# Sheet2.net
KiCad netlist of a schematic drawn in Altium Designer
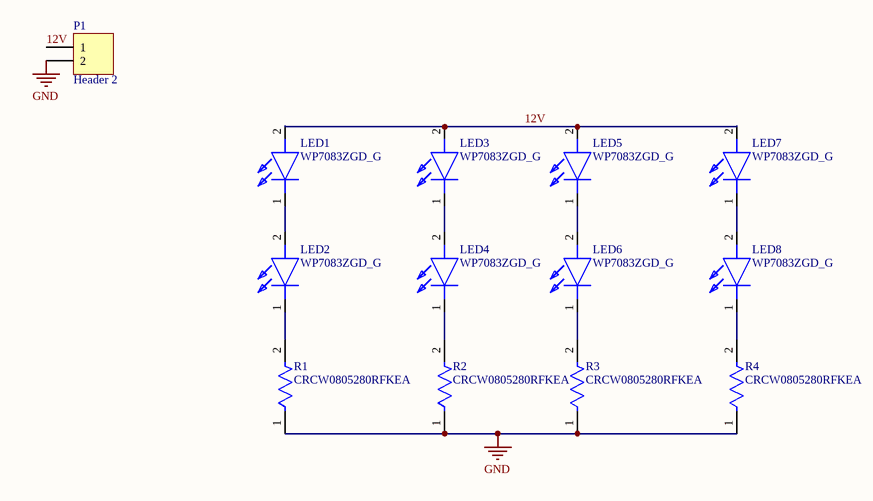
[diagram p0: Sheet2.SchDoc]

(export (version "E")
  (design (tool "Eeschema 10.0.6"))
  (components
    (comp (ref "LED1")
      (value "WP7083ZGD_G")
      (footprint "SamacSys:L53ND")
      (description "LED")
      (fields
        (field (name "MANUFACTURER_PART_NUMBER") "WP7083ZGD/G")
        (field (name "MOUSER PART NUMBER") "604-WP7083ZGD/G")
      )
      (libsource (lib "*") (part "WP7083ZGD_G"))
    )
    (comp (ref "LED2")
      (value "WP7083ZGD_G")
      (footprint "SamacSys:L53ND")
      (description "LED")
      (fields
        (field (name "MANUFACTURER_PART_NUMBER") "WP7083ZGD/G")
        (field (name "MOUSER PART NUMBER") "604-WP7083ZGD/G")
      )
      (libsource (lib "*") (part "WP7083ZGD_G"))
    )
    (comp (ref "LED3")
      (value "WP7083ZGD_G")
      (footprint "SamacSys:L53ND")
      (description "LED")
      (fields
        (field (name "MANUFACTURER_PART_NUMBER") "WP7083ZGD/G")
        (field (name "MOUSER PART NUMBER") "604-WP7083ZGD/G")
      )
      (libsource (lib "*") (part "WP7083ZGD_G"))
    )
    (comp (ref "LED4")
      (value "WP7083ZGD_G")
      (footprint "SamacSys:L53ND")
      (description "LED")
      (fields
        (field (name "MANUFACTURER_PART_NUMBER") "WP7083ZGD/G")
        (field (name "MOUSER PART NUMBER") "604-WP7083ZGD/G")
      )
      (libsource (lib "*") (part "WP7083ZGD_G"))
    )
    (comp (ref "LED5")
      (value "WP7083ZGD_G")
      (footprint "SamacSys:L53ND")
      (description "LED")
      (fields
        (field (name "MANUFACTURER_PART_NUMBER") "WP7083ZGD/G")
        (field (name "MOUSER PART NUMBER") "604-WP7083ZGD/G")
      )
      (libsource (lib "*") (part "WP7083ZGD_G"))
    )
    (comp (ref "LED6")
      (value "WP7083ZGD_G")
      (footprint "SamacSys:L53ND")
      (description "LED")
      (fields
        (field (name "MANUFACTURER_PART_NUMBER") "WP7083ZGD/G")
        (field (name "MOUSER PART NUMBER") "604-WP7083ZGD/G")
      )
      (libsource (lib "*") (part "WP7083ZGD_G"))
    )
    (comp (ref "LED7")
      (value "WP7083ZGD_G")
      (footprint "SamacSys:L53ND")
      (description "LED")
      (fields
        (field (name "MANUFACTURER_PART_NUMBER") "WP7083ZGD/G")
        (field (name "MOUSER PART NUMBER") "604-WP7083ZGD/G")
      )
      (libsource (lib "*") (part "WP7083ZGD_G"))
    )
    (comp (ref "LED8")
      (value "WP7083ZGD_G")
      (footprint "SamacSys:L53ND")
      (description "LED")
      (fields
        (field (name "MANUFACTURER_PART_NUMBER") "WP7083ZGD/G")
        (field (name "MOUSER PART NUMBER") "604-WP7083ZGD/G")
      )
      (libsource (lib "*") (part "WP7083ZGD_G"))
    )
    (comp (ref "P1")
      (value "Header 2")
      (footprint "HDR1X2")
      (description "Header, 2-Pin")
      (fields (field (name "PUBLISHER") "Altium Limited"))
      (libsource (lib "Miscellaneous Connectors") (part "Header 2"))
    )
    (comp (ref "R1")
      (value "CRCW0805280RFKEA")
      (footprint "FP-CRCW0805-e3-MFG")
      (description "RES Thick Film, 280Ω, 1%, 0.125W, 100ppm/°C, 0805")
      (fields (field (name "TOLERANCE") "1%"))
      (libsource (lib "Altium Content Vault") (part "1029c3af85768c4190bb7ad29bc67b5"))
    )
    (comp (ref "R2")
      (value "CRCW0805280RFKEA")
      (footprint "FP-CRCW0805-e3-MFG")
      (description "RES Thick Film, 280Ω, 1%, 0.125W, 100ppm/°C, 0805")
      (fields (field (name "TOLERANCE") "1%"))
      (libsource (lib "Altium Content Vault") (part "1029c3af85768c4190bb7ad29bc67b5"))
    )
    (comp (ref "R3")
      (value "CRCW0805280RFKEA")
      (footprint "FP-CRCW0805-e3-MFG")
      (description "RES Thick Film, 280Ω, 1%, 0.125W, 100ppm/°C, 0805")
      (fields (field (name "TOLERANCE") "1%"))
      (libsource (lib "Altium Content Vault") (part "1029c3af85768c4190bb7ad29bc67b5"))
    )
    (comp (ref "R4")
      (value "CRCW0805280RFKEA")
      (footprint "FP-CRCW0805-e3-MFG")
      (description "RES Thick Film, 280Ω, 1%, 0.125W, 100ppm/°C, 0805")
      (fields (field (name "TOLERANCE") "1%"))
      (libsource (lib "Altium Content Vault") (part "1029c3af85768c4190bb7ad29bc67b5"))
    )
  )
  (nets
    (net (code "1") (name "/12V") (class "Default")
      (node (ref "LED1") (pin "2") (pinfunction "A_2") (pintype "passive"))
      (node (ref "LED3") (pin "2") (pinfunction "A_2") (pintype "passive"))
      (node (ref "LED5") (pin "2") (pinfunction "A_2") (pintype "passive"))
      (node (ref "LED7") (pin "2") (pinfunction "A_2") (pintype "passive"))
      (node (ref "P1") (pin "1") (pinfunction "1_1") (pintype "passive"))
    )
    (net (code "2") (name "GND") (class "Default")
      (node (ref "P1") (pin "2") (pinfunction "2_2") (pintype "passive"))
      (node (ref "R1") (pin "1") (pinfunction "1_1") (pintype "passive"))
      (node (ref "R2") (pin "1") (pinfunction "1_1") (pintype "passive"))
      (node (ref "R3") (pin "1") (pinfunction "1_1") (pintype "passive"))
      (node (ref "R4") (pin "1") (pinfunction "1_1") (pintype "passive"))
    )
    (net (code "3") (name "Net-(LED1-K)") (class "Default")
      (node (ref "LED1") (pin "1") (pinfunction "K_1") (pintype "passive"))
      (node (ref "LED2") (pin "2") (pinfunction "A_2") (pintype "passive"))
    )
    (net (code "4") (name "Net-(LED2-K)") (class "Default")
      (node (ref "LED2") (pin "1") (pinfunction "K_1") (pintype "passive"))
      (node (ref "R1") (pin "2") (pinfunction "2_2") (pintype "passive"))
    )
    (net (code "5") (name "Net-(LED3-K)") (class "Default")
      (node (ref "LED3") (pin "1") (pinfunction "K_1") (pintype "passive"))
      (node (ref "LED4") (pin "2") (pinfunction "A_2") (pintype "passive"))
    )
    (net (code "6") (name "Net-(LED4-K)") (class "Default")
      (node (ref "LED4") (pin "1") (pinfunction "K_1") (pintype "passive"))
      (node (ref "R2") (pin "2") (pinfunction "2_2") (pintype "passive"))
    )
    (net (code "7") (name "Net-(LED5-K)") (class "Default")
      (node (ref "LED5") (pin "1") (pinfunction "K_1") (pintype "passive"))
      (node (ref "LED6") (pin "2") (pinfunction "A_2") (pintype "passive"))
    )
    (net (code "8") (name "Net-(LED6-K)") (class "Default")
      (node (ref "LED6") (pin "1") (pinfunction "K_1") (pintype "passive"))
      (node (ref "R3") (pin "2") (pinfunction "2_2") (pintype "passive"))
    )
    (net (code "9") (name "Net-(LED7-K)") (class "Default")
      (node (ref "LED7") (pin "1") (pinfunction "K_1") (pintype "passive"))
      (node (ref "LED8") (pin "2") (pinfunction "A_2") (pintype "passive"))
    )
    (net (code "10") (name "Net-(LED8-K)") (class "Default")
      (node (ref "LED8") (pin "1") (pinfunction "K_1") (pintype "passive"))
      (node (ref "R4") (pin "2") (pinfunction "2_2") (pintype "passive"))
    )
  )
)
